# ESP8266.net
KiCad netlist of a schematic drawn in Altium Designer
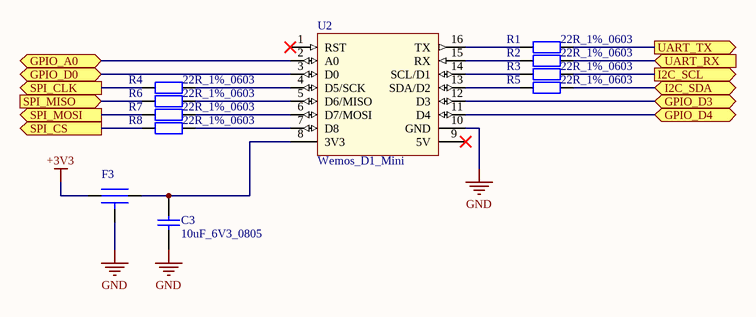
[diagram p0: ESP8266.SchDoc]

(export (version "E")
  (design (tool "Eeschema 10.0.6"))
  (components
    (comp (ref "C3")
      (value "10uF_6V3_0805")
      (footprint "Common:C0805")
      (description "Capacitor")
      (fields (field (name "MF") " MULTICOMP") (field (name "MPN") "MCTT21X106M6R3CT"))
      (libsource (lib "Common") (part "Cap"))
    )
    (comp (ref "F3")
      (value "EMI")
      (footprint "EMIFIL_0603")
      (description "FILTER CAP 0.1UF 2A 16V 0603")
      (fields (field (name "MF") "MURATA") (field (name "MPN") "NFM18PC104R1C3D"))
      (libsource (lib "Common") (part "EMIFIL_0603"))
    )
    (comp (ref "R1")
      (value "22R_1%_0603")
      (footprint "R0603")
      (description "Resistor")
      (fields (field (name "MF") "Multicomp") (field (name "MPN") "MCWR06X22R0FTL"))
      (libsource (lib "Common") (part "RES"))
    )
    (comp (ref "R2")
      (value "22R_1%_0603")
      (footprint "R0603")
      (description "Resistor")
      (fields (field (name "MF") "Multicomp") (field (name "MPN") "MCWR06X22R0FTL"))
      (libsource (lib "Common") (part "RES"))
    )
    (comp (ref "R3")
      (value "22R_1%_0603")
      (footprint "R0603")
      (description "Resistor")
      (fields (field (name "MF") "Multicomp") (field (name "MPN") "MCWR06X22R0FTL"))
      (libsource (lib "Common") (part "RES"))
    )
    (comp (ref "R4")
      (value "22R_1%_0603")
      (footprint "R0603")
      (description "Resistor")
      (fields (field (name "MF") "Multicomp") (field (name "MPN") "MCWR06X22R0FTL"))
      (libsource (lib "Common") (part "RES"))
    )
    (comp (ref "R5")
      (value "22R_1%_0603")
      (footprint "R0603")
      (description "Resistor")
      (fields (field (name "MF") "Multicomp") (field (name "MPN") "MCWR06X22R0FTL"))
      (libsource (lib "Common") (part "RES"))
    )
    (comp (ref "R6")
      (value "22R_1%_0603")
      (footprint "R0603")
      (description "Resistor")
      (fields (field (name "MF") "Multicomp") (field (name "MPN") "MCWR06X22R0FTL"))
      (libsource (lib "Common") (part "RES"))
    )
    (comp (ref "R7")
      (value "22R_1%_0603")
      (footprint "R0603")
      (description "Resistor")
      (fields (field (name "MF") "Multicomp") (field (name "MPN") "MCWR06X22R0FTL"))
      (libsource (lib "Common") (part "RES"))
    )
    (comp (ref "R8")
      (value "22R_1%_0603")
      (footprint "R0603")
      (description "Resistor")
      (fields (field (name "MF") "Multicomp") (field (name "MPN") "MCWR06X22R0FTL"))
      (libsource (lib "Common") (part "RES"))
    )
    (comp (ref "U2")
      (value "Wemos_D1_Mini")
      (footprint "WEMOS_D1_MINI")
      (libsource (lib "Common") (part "ESP8266"))
    )
  )
  (nets
    (net (code "1") (name "+3V3") (class "Default")
      (node (ref "F3") (pin "2") (pinfunction "2_2") (pintype "passive"))
    )
    (net (code "2") (name "/GPIO_A0") (class "Default")
      (node (ref "U2") (pin "2") (pinfunction "A0_2") (pintype "bidirectional"))
    )
    (net (code "3") (name "/GPIO_D0") (class "Default")
      (node (ref "U2") (pin "3") (pinfunction "D0_3") (pintype "bidirectional"))
    )
    (net (code "4") (name "/GPIO_D3") (class "Default")
      (node (ref "U2") (pin "12") (pinfunction "D3_12") (pintype "bidirectional"))
    )
    (net (code "5") (name "/GPIO_D4") (class "Default")
      (node (ref "U2") (pin "11") (pinfunction "D4_11") (pintype "bidirectional"))
    )
    (net (code "6") (name "/I2C_SCL") (class "Default")
      (node (ref "R3") (pin "2") (pinfunction "2_2") (pintype "passive"))
    )
    (net (code "7") (name "/I2C_SDA") (class "Default")
      (node (ref "R5") (pin "2") (pinfunction "2_2") (pintype "passive"))
    )
    (net (code "8") (name "/SPI_CLK") (class "Default")
      (node (ref "R4") (pin "1") (pinfunction "1_1") (pintype "passive"))
    )
    (net (code "9") (name "/SPI_CS") (class "Default")
      (node (ref "R8") (pin "1") (pinfunction "1_1") (pintype "passive"))
    )
    (net (code "10") (name "/SPI_MISO") (class "Default")
      (node (ref "R6") (pin "1") (pinfunction "1_1") (pintype "passive"))
    )
    (net (code "11") (name "/SPI_MOSI") (class "Default")
      (node (ref "R7") (pin "1") (pinfunction "1_1") (pintype "passive"))
    )
    (net (code "12") (name "/UART_RX") (class "Default")
      (node (ref "R2") (pin "2") (pinfunction "2_2") (pintype "passive"))
    )
    (net (code "13") (name "/UART_TX") (class "Default")
      (node (ref "R1") (pin "2") (pinfunction "2_2") (pintype "passive"))
    )
    (net (code "14") (name "GND") (class "Default")
      (node (ref "C3") (pin "1") (pinfunction "1_1") (pintype "passive"))
      (node (ref "F3") (pin "GND") (pinfunction "GND_GND") (pintype "passive"))
      (node (ref "U2") (pin "10") (pinfunction "GND_10") (pintype "power_in"))
    )
    (net (code "15") (name "Net-(U2-3V3)") (class "Default")
      (node (ref "C3") (pin "2") (pinfunction "2_2") (pintype "passive"))
      (node (ref "F3") (pin "1") (pinfunction "1_1") (pintype "passive"))
      (node (ref "U2") (pin "8") (pinfunction "3V3_8") (pintype "power_in"))
    )
    (net (code "16") (name "Net-(U2-D5{slash}SCK)") (class "Default")
      (node (ref "R4") (pin "2") (pinfunction "2_2") (pintype "passive"))
      (node (ref "U2") (pin "4") (pinfunction "D5/SCK_4") (pintype "bidirectional"))
    )
    (net (code "17") (name "Net-(U2-D6{slash}MISO)") (class "Default")
      (node (ref "R6") (pin "2") (pinfunction "2_2") (pintype "passive"))
      (node (ref "U2") (pin "5") (pinfunction "D6/MISO_5") (pintype "bidirectional"))
    )
    (net (code "18") (name "Net-(U2-D7{slash}MOSI)") (class "Default")
      (node (ref "R7") (pin "2") (pinfunction "2_2") (pintype "passive"))
      (node (ref "U2") (pin "6") (pinfunction "D7/MOSI_6") (pintype "bidirectional"))
    )
    (net (code "19") (name "Net-(U2-D8)") (class "Default")
      (node (ref "R8") (pin "2") (pinfunction "2_2") (pintype "passive"))
      (node (ref "U2") (pin "7") (pinfunction "D8_7") (pintype "bidirectional"))
    )
    (net (code "20") (name "Net-(U2-RX)") (class "Default")
      (node (ref "R2") (pin "1") (pinfunction "1_1") (pintype "passive"))
      (node (ref "U2") (pin "15") (pinfunction "RX_15") (pintype "input"))
    )
    (net (code "21") (name "Net-(U2-SCL{slash}D1)") (class "Default")
      (node (ref "R3") (pin "1") (pinfunction "1_1") (pintype "passive"))
      (node (ref "U2") (pin "14") (pinfunction "SCL/D1_14") (pintype "bidirectional"))
    )
    (net (code "22") (name "Net-(U2-SDA{slash}D2)") (class "Default")
      (node (ref "R5") (pin "1") (pinfunction "1_1") (pintype "passive"))
      (node (ref "U2") (pin "13") (pinfunction "SDA/D2_13") (pintype "bidirectional"))
    )
    (net (code "23") (name "Net-(U2-TX)") (class "Default")
      (node (ref "R1") (pin "1") (pinfunction "1_1") (pintype "passive"))
      (node (ref "U2") (pin "16") (pinfunction "TX_16") (pintype "output"))
    )
    (net (code "24") (name "unconnected-(U2-5V-Pad9)") (class "Default")
      (node (ref "U2") (pin "9") (pinfunction "5V_9") (pintype "power_in+no_connect"))
    )
    (net (code "25") (name "unconnected-(U2-RST-Pad1)") (class "Default")
      (node (ref "U2") (pin "1") (pinfunction "RST_1") (pintype "input+no_connect"))
    )
  )
)
